# Sheet2.net
KiCad netlist of a schematic drawn in Altium Designer
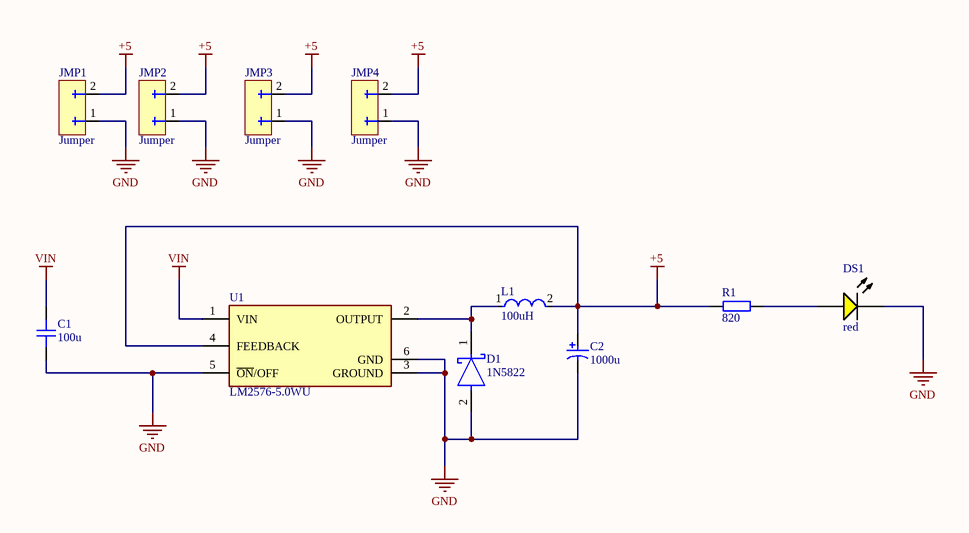
[diagram p0: Sheet2.SchDoc]

(export (version "E")
  (design (tool "Eeschema 10.0.6"))
  (components
    (comp (ref "C1")
      (value "100u")
      (footprint "CAP_1206")
      (description "Capacitor SMD 1206")
      (libsource (lib "Schematic-Lib-PhilsLab") (part "CAP_1206"))
    )
    (comp (ref "C2")
      (value "1000u")
      (footprint "NIC-UCL-10x13.5-2_V")
      (fields (field (name "MANUFACTURER") "Nichicon") (field (name "PARTNUMBER") "UCL1C102MNL1GS"))
      (libsource (lib "Altium Content Vault") (part "NIC-CAP-P-2"))
    )
    (comp (ref "D1")
      (value "1N5822")
      (footprint "FP-DO-201AD-MFG")
      (description "DIODE SCHOTTKY 40V 3A DO201AD")
      (fields
        (field (name "OCTOPART") "https://octopart.com/1n5822-stmicroelectronics-323225")
        (field (name "MANUFACTURER") "STMicroelectronics")
      )
      (libsource (lib "Altium Content Vault") (part "1d6ec82d83fb6aee721767c19dac4b9"))
    )
    (comp (ref "DS1")
      (value "red")
      (footprint "LUMX-SML-LX1206YC-TR_V")
      (description "Yellow LED, Water Clear Len, 585 nm, 2.1 V, -40 to 85 degC, 2-Pin SMD, RoHS, Tape and Reel")
      (fields (field (name "MANUFACTURER") "Lumex"))
      (libsource (lib "Altium Content Vault") (part "LED-YELLOW-AK-2"))
    )
    (comp (ref "JMP1")
      (value "Jumper")
      (footprint "JMP2_TH")
      (description "Jumper 2 Pins Through-Hole DO NOT PLACE")
      (libsource (lib "Schematic-Lib-PhilsLab") (part "JMP2_TH"))
    )
    (comp (ref "JMP2")
      (value "Jumper")
      (footprint "JMP2_TH")
      (description "Jumper 2 Pins Through-Hole DO NOT PLACE")
      (libsource (lib "Schematic-Lib-PhilsLab") (part "JMP2_TH"))
    )
    (comp (ref "JMP3")
      (value "Jumper")
      (footprint "JMP2_TH")
      (description "Jumper 2 Pins Through-Hole DO NOT PLACE")
      (libsource (lib "Schematic-Lib-PhilsLab") (part "JMP2_TH"))
    )
    (comp (ref "JMP4")
      (value "Jumper")
      (footprint "JMP2_TH")
      (description "Jumper 2 Pins Through-Hole DO NOT PLACE")
      (libsource (lib "Schematic-Lib-PhilsLab") (part "JMP2_TH"))
    )
    (comp (ref "L1")
      (value "100uH")
      (footprint "FP-IHLP-6767GZ-FP_3_825x1-MFG")
      (description "Commercial Inductors, Low DCR Series 100uH 5A 110mΩ 20%")
      (fields (field (name "TOLERANCE") "20%"))
      (libsource (lib "Altium Content Vault") (part "725321dda6339637d4d059423bc1c3c"))
    )
    (comp (ref "R1")
      (value "820")
      (footprint "RES_1206")
      (description "Resistor SMD 1206")
      (libsource (lib "Schematic-Lib-PhilsLab") (part "RES_1206"))
    )
    (comp (ref "U1")
      (value "LM2576-5.0WU")
      (footprint "FP-TO263-5LD-PL-1-MFG")
      (description "IC REG BUCK 5V 3A TO263-5")
      (libsource (lib "Altium Content Vault") (part "696d7d971c3ca261a0c8f70d528ffc3"))
    )
  )
  (nets
    (net (code "1") (name "+5") (class "Default")
      (node (ref "C2") (pin "1") (pinfunction "1_1") (pintype "passive"))
      (node (ref "JMP1") (pin "2") (pinfunction "2_2") (pintype "passive"))
      (node (ref "JMP2") (pin "2") (pinfunction "2_2") (pintype "passive"))
      (node (ref "JMP3") (pin "2") (pinfunction "2_2") (pintype "passive"))
      (node (ref "JMP4") (pin "2") (pinfunction "2_2") (pintype "passive"))
      (node (ref "L1") (pin "2") (pinfunction "2_2") (pintype "passive"))
      (node (ref "R1") (pin "1") (pinfunction "1_1") (pintype "passive"))
      (node (ref "U1") (pin "4") (pinfunction "FEEDBACK_4") (pintype "passive"))
    )
    (net (code "2") (name "GND") (class "Default")
      (node (ref "C1") (pin "1") (pinfunction "1_1") (pintype "passive"))
      (node (ref "C2") (pin "2") (pinfunction "2_2") (pintype "passive"))
      (node (ref "D1") (pin "2") (pinfunction "A_2") (pintype "passive"))
      (node (ref "DS1") (pin "2") (pinfunction "K_2") (pintype "passive"))
      (node (ref "JMP1") (pin "1") (pinfunction "1_1") (pintype "passive"))
      (node (ref "JMP2") (pin "1") (pinfunction "1_1") (pintype "passive"))
      (node (ref "JMP3") (pin "1") (pinfunction "1_1") (pintype "passive"))
      (node (ref "JMP4") (pin "1") (pinfunction "1_1") (pintype "passive"))
      (node (ref "U1") (pin "3") (pinfunction "GROUND_3") (pintype "power_in"))
      (node (ref "U1") (pin "5") (pinfunction "~{ON}/OFF_5") (pintype "passive"))
      (node (ref "U1") (pin "6") (pinfunction "GND_6") (pintype "power_in"))
    )
    (net (code "3") (name "Net-(D1-C)") (class "Default")
      (node (ref "D1") (pin "1") (pinfunction "C_1") (pintype "passive"))
      (node (ref "L1") (pin "1") (pinfunction "1_1") (pintype "passive"))
      (node (ref "U1") (pin "2") (pinfunction "OUTPUT_2") (pintype "power_in"))
    )
    (net (code "4") (name "Net-(DS1-A)") (class "Default")
      (node (ref "DS1") (pin "1") (pinfunction "A_1") (pintype "passive"))
      (node (ref "R1") (pin "2") (pinfunction "2_2") (pintype "passive"))
    )
    (net (code "5") (name "VIN") (class "Default")
      (node (ref "C1") (pin "2") (pinfunction "2_2") (pintype "passive"))
      (node (ref "U1") (pin "1") (pinfunction "VIN_1") (pintype "power_in"))
    )
  )
)
